# inhibits2.net
KiCad netlist of a schematic drawn in Altium Designer
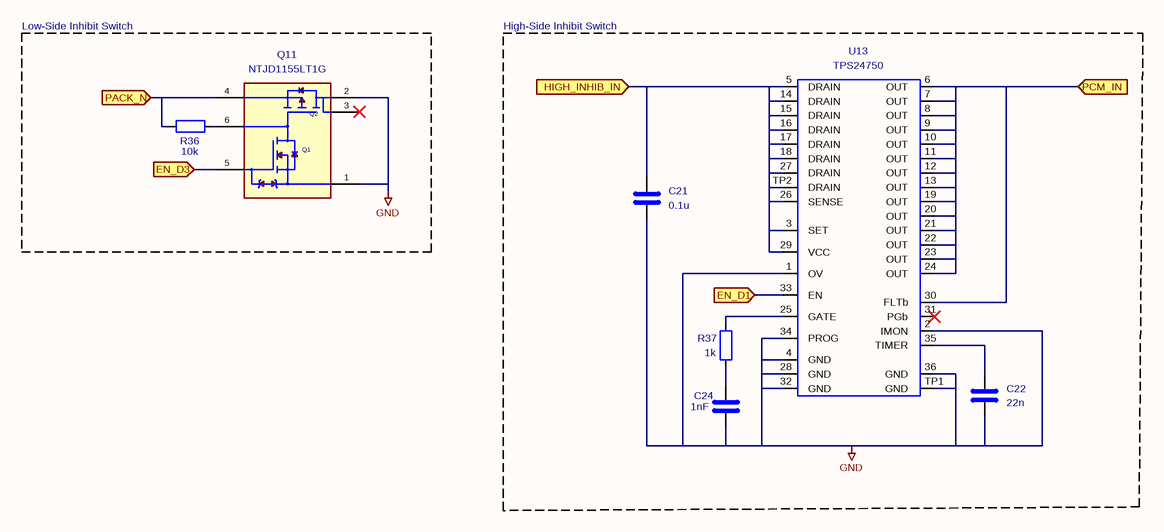
[diagram p0: inhibits2.SchDoc]

(export (version "E")
  (design (tool "Eeschema 10.0.6"))
  (components
    (comp (ref "C21") (value "0.1u") (libsource (lib "Device") (part "C")))
    (comp (ref "C22") (value "22n") (libsource (lib "Device") (part "C")))
    (comp (ref "C24") (value "1nF") (libsource (lib "Device") (part "C")))
    (comp (ref "Q11")
      (value "NTJD1155LT1G")
      (fields (field (name "MANUFACTURER") "ON Semiconductor"))
      (libsource (lib "NTJD1155LT1G") (part "NTJD1155LT1G"))
    )
    (comp (ref "R36") (value "10k") (libsource (lib "Device") (part "R")))
    (comp (ref "R37") (value "1k") (libsource (lib "") (part "R_1")))
    (comp (ref "U13") (value "TPS24750") (libsource (lib "TPS24750") (part "TPS24750")))
  )
  (nets
    (net (code "1") (name "/EN_D1") (class "Default")
      (node (ref "U13") (pin "33") (pinfunction "EN_33") (pintype "passive"))
    )
    (net (code "2") (name "/EN_D3") (class "Default")
      (node (ref "Q11") (pin "5") (pinfunction "5_5") (pintype "passive"))
    )
    (net (code "3") (name "/HIGH_INHIB_IN") (class "Default")
      (node (ref "C21") (pin "1") (pinfunction "1_1") (pintype "passive"))
      (node (ref "U13") (pin "14") (pinfunction "DRAIN_14") (pintype "passive"))
      (node (ref "U13") (pin "15") (pinfunction "DRAIN_15") (pintype "passive"))
      (node (ref "U13") (pin "16") (pinfunction "DRAIN_16") (pintype "passive"))
      (node (ref "U13") (pin "17") (pinfunction "DRAIN_17") (pintype "passive"))
      (node (ref "U13") (pin "18") (pinfunction "DRAIN_18") (pintype "passive"))
      (node (ref "U13") (pin "26") (pinfunction "SENSE_26") (pintype "passive"))
      (node (ref "U13") (pin "27") (pinfunction "DRAIN_27") (pintype "passive"))
      (node (ref "U13") (pin "29") (pinfunction "VCC_29") (pintype "passive"))
      (node (ref "U13") (pin "3") (pinfunction "SET_3") (pintype "passive"))
      (node (ref "U13") (pin "5") (pinfunction "DRAIN_5") (pintype "passive"))
      (node (ref "U13") (pin "TP2") (pinfunction "DRAIN_TP2") (pintype "passive"))
    )
    (net (code "4") (name "/PACK_N") (class "Default")
      (node (ref "Q11") (pin "4") (pinfunction "4_4") (pintype "passive"))
      (node (ref "R36") (pin "1") (pinfunction "1_1") (pintype "passive"))
    )
    (net (code "5") (name "/PCM_IN") (class "Default")
      (node (ref "U13") (pin "10") (pinfunction "OUT_10") (pintype "passive"))
      (node (ref "U13") (pin "11") (pinfunction "OUT_11") (pintype "passive"))
      (node (ref "U13") (pin "12") (pinfunction "OUT_12") (pintype "passive"))
      (node (ref "U13") (pin "13") (pinfunction "OUT_13") (pintype "passive"))
      (node (ref "U13") (pin "19") (pinfunction "OUT_19") (pintype "passive"))
      (node (ref "U13") (pin "20") (pinfunction "OUT_20") (pintype "passive"))
      (node (ref "U13") (pin "21") (pinfunction "OUT_21") (pintype "passive"))
      (node (ref "U13") (pin "22") (pinfunction "OUT_22") (pintype "passive"))
      (node (ref "U13") (pin "23") (pinfunction "OUT_23") (pintype "passive"))
      (node (ref "U13") (pin "24") (pinfunction "OUT_24") (pintype "passive"))
      (node (ref "U13") (pin "30") (pinfunction "FLTb_30") (pintype "passive"))
      (node (ref "U13") (pin "6") (pinfunction "OUT_6") (pintype "passive"))
      (node (ref "U13") (pin "7") (pinfunction "OUT_7") (pintype "passive"))
      (node (ref "U13") (pin "8") (pinfunction "OUT_8") (pintype "passive"))
      (node (ref "U13") (pin "9") (pinfunction "OUT_9") (pintype "passive"))
    )
    (net (code "6") (name "GND") (class "Default")
      (node (ref "C21") (pin "2") (pinfunction "2_2") (pintype "passive"))
      (node (ref "C22") (pin "2") (pinfunction "2_2") (pintype "passive"))
      (node (ref "C24") (pin "2") (pinfunction "2_2") (pintype "passive"))
      (node (ref "Q11") (pin "1") (pinfunction "1_1") (pintype "passive"))
      (node (ref "Q11") (pin "2") (pinfunction "2_2") (pintype "passive"))
      (node (ref "U13") (pin "1") (pinfunction "OV_1") (pintype "passive"))
      (node (ref "U13") (pin "2") (pinfunction "IMON_2") (pintype "passive"))
      (node (ref "U13") (pin "28") (pinfunction "GND_28") (pintype "passive"))
      (node (ref "U13") (pin "32") (pinfunction "GND_32") (pintype "passive"))
      (node (ref "U13") (pin "34") (pinfunction "PROG_34") (pintype "passive"))
      (node (ref "U13") (pin "36") (pinfunction "GND_36") (pintype "passive"))
      (node (ref "U13") (pin "4") (pinfunction "GND_4") (pintype "passive"))
      (node (ref "U13") (pin "TP1") (pinfunction "GND_TP1") (pintype "passive"))
    )
    (net (code "7") (name "Net-(C24-Pad1)") (class "Default")
      (node (ref "C24") (pin "1") (pinfunction "1_1") (pintype "passive"))
      (node (ref "R37") (pin "2") (pinfunction "2_2") (pintype "passive"))
    )
    (net (code "8") (name "Net-(Q11-Pad6)") (class "Default")
      (node (ref "Q11") (pin "6") (pinfunction "6_6") (pintype "passive"))
      (node (ref "R36") (pin "2") (pinfunction "2_2") (pintype "passive"))
    )
    (net (code "9") (name "Net-(U13-GATE)") (class "Default")
      (node (ref "R37") (pin "1") (pinfunction "1_1") (pintype "passive"))
      (node (ref "U13") (pin "25") (pinfunction "GATE_25") (pintype "passive"))
    )
    (net (code "10") (name "Net-(U13-TIMER)") (class "Default")
      (node (ref "C22") (pin "1") (pinfunction "1_1") (pintype "passive"))
      (node (ref "U13") (pin "35") (pinfunction "TIMER_35") (pintype "passive"))
    )
    (net (code "11") (name "unconnected-(Q11-Pad3)") (class "Default")
      (node (ref "Q11") (pin "3") (pinfunction "3_3") (pintype "passive+no_connect"))
    )
    (net (code "12") (name "unconnected-(U13-PGb-Pad31)") (class "Default")
      (node (ref "U13") (pin "31") (pinfunction "PGb_31") (pintype "passive+no_connect"))
    )
  )
)
